# nRF52832_qfaa.net
KiCad netlist of a schematic drawn in EAGLE
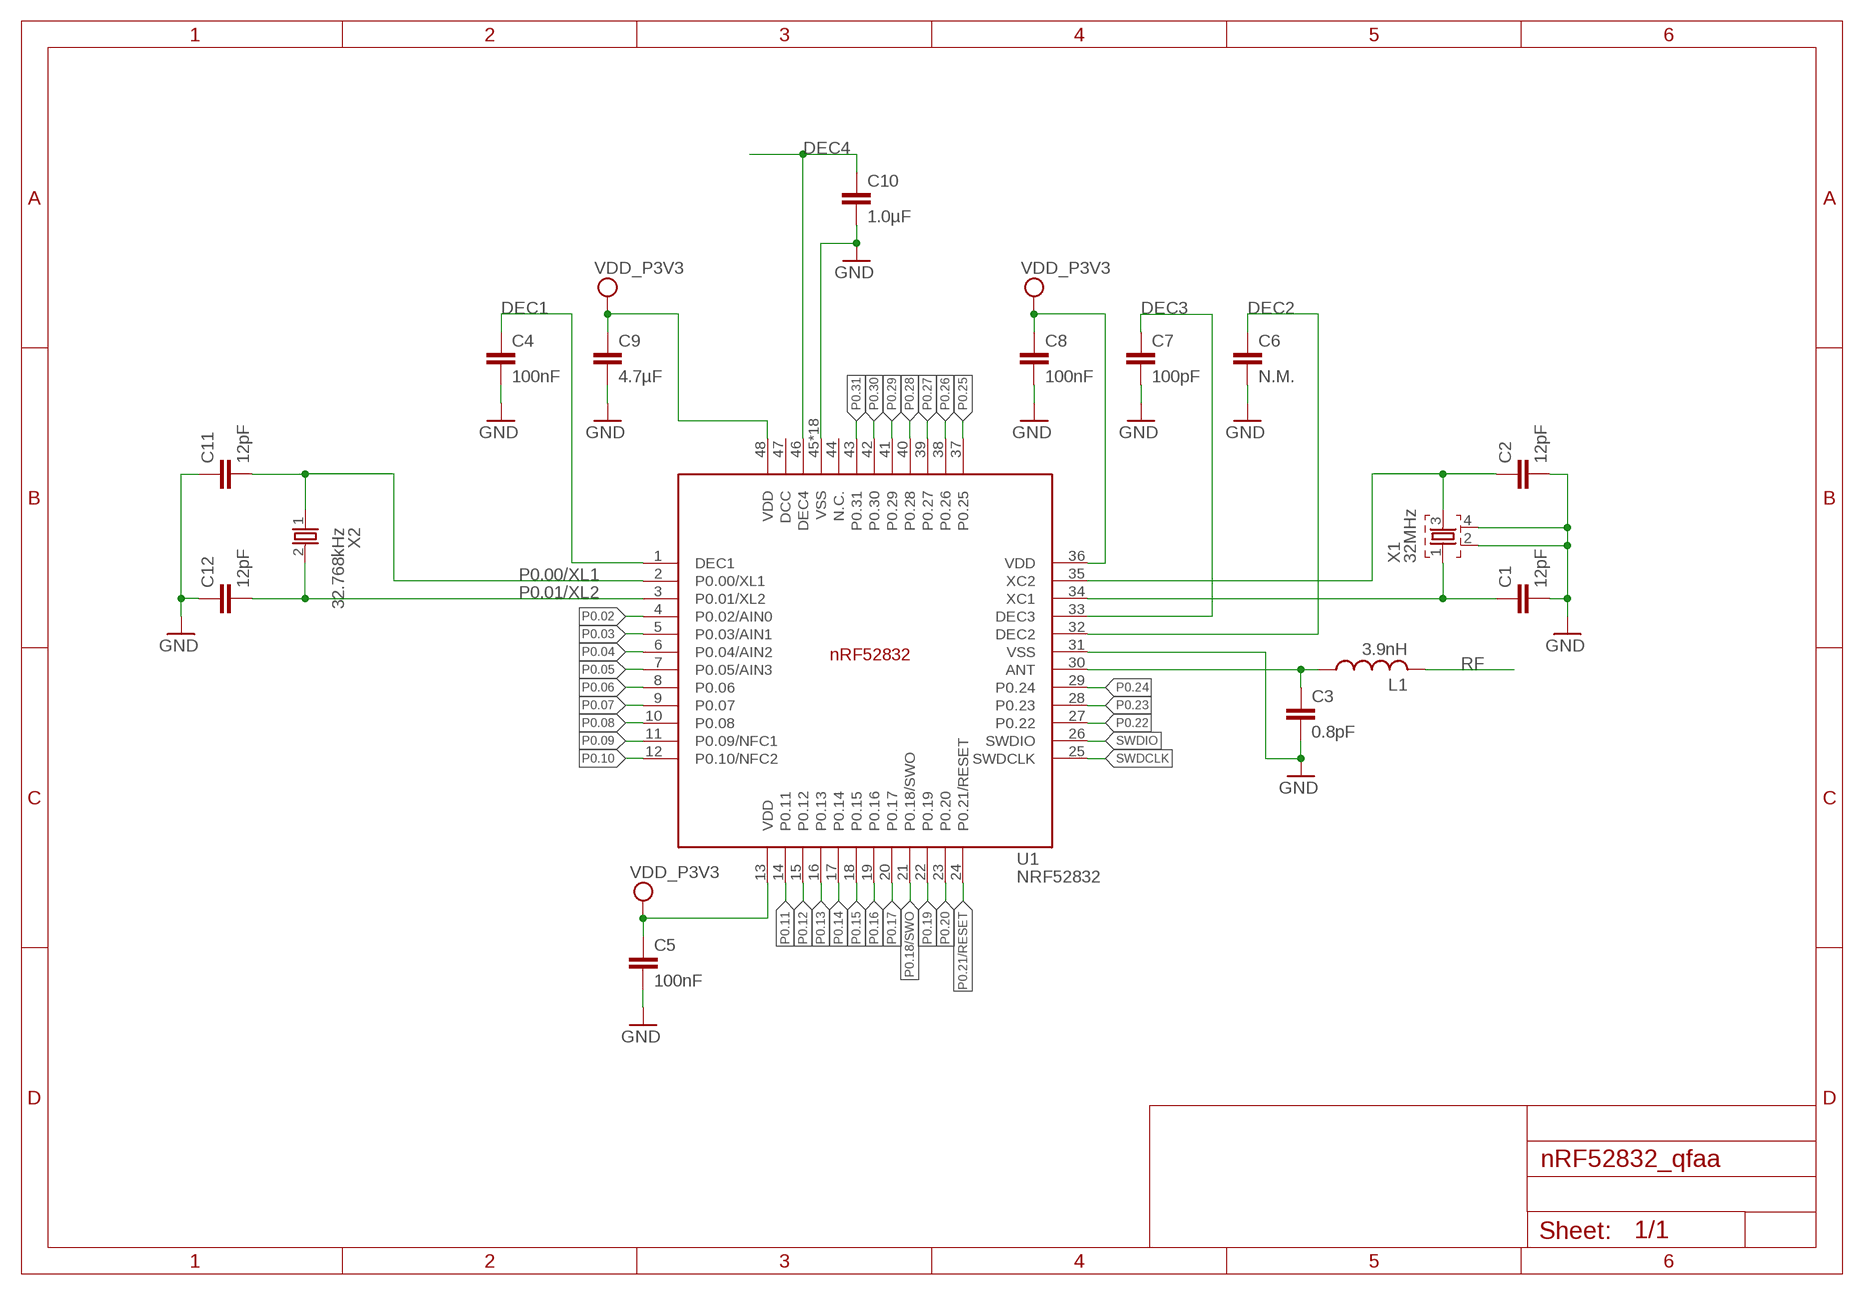
[diagram p0: schematic, sheet 1]

(export (version "E")
  (design (tool "Eeschema 10.0.6"))
  (components
    (comp (ref "C1")
      (value "12pF")
      (footprint "eagle-import:RESC0402_N")
      (libsource (lib "eagle-import") (part "CAPACITOR_0402_N"))
    )
    (comp (ref "C2")
      (value "12pF")
      (footprint "eagle-import:RESC0402_N")
      (libsource (lib "eagle-import") (part "CAPACITOR_0402_N"))
    )
    (comp (ref "C3")
      (value "0.8pF")
      (footprint "eagle-import:RESC0402_N")
      (libsource (lib "eagle-import") (part "CAPACITOR_0402_N"))
    )
    (comp (ref "C4")
      (value "100nF")
      (footprint "eagle-import:RESC0402_N")
      (libsource (lib "eagle-import") (part "CAPACITOR_0402_N"))
    )
    (comp (ref "C5")
      (value "100nF")
      (footprint "eagle-import:RESC0402_N")
      (libsource (lib "eagle-import") (part "CAPACITOR_0402_N"))
    )
    (comp (ref "C6")
      (value "N.M.")
      (footprint "eagle-import:RESC0402_N")
      (libsource (lib "eagle-import") (part "CAPACITOR_0402_N"))
    )
    (comp (ref "C7")
      (value "100pF")
      (footprint "eagle-import:RESC0402_N")
      (libsource (lib "eagle-import") (part "CAPACITOR_0402_N"))
    )
    (comp (ref "C8")
      (value "100nF")
      (footprint "eagle-import:RESC0402_N")
      (libsource (lib "eagle-import") (part "CAPACITOR_0402_N"))
    )
    (comp (ref "C9")
      (value "4.7µF")
      (footprint "eagle-import:RESC0603_N")
      (libsource (lib "eagle-import") (part "CAPACITOR_0603_N"))
    )
    (comp (ref "C10")
      (value "1.0µF")
      (footprint "eagle-import:RESC0603_N")
      (libsource (lib "eagle-import") (part "CAPACITOR_0603_N"))
    )
    (comp (ref "C11")
      (value "12pF")
      (footprint "eagle-import:RESC0402_N")
      (libsource (lib "eagle-import") (part "CAPACITOR_0402_N"))
    )
    (comp (ref "C12")
      (value "12pF")
      (footprint "eagle-import:RESC0402_N")
      (libsource (lib "eagle-import") (part "CAPACITOR_0402_N"))
    )
    (comp (ref "L1")
      (value "3.9nH")
      (footprint "eagle-import:RESC0402_N")
      (libsource (lib "eagle-import") (part "INDUCTOR_0402_N"))
    )
    (comp (ref "U1")
      (value "NRF52832")
      (footprint "eagle-import:QFN40P600X600X90-48_N")
      (libsource (lib "eagle-import") (part "NRF52832"))
    )
    (comp (ref "X1")
      (value "32MHz")
      (footprint "eagle-import:BT-XTAL_2016_N")
      (libsource (lib "eagle-import") (part "XTAL_32MHZ"))
    )
    (comp (ref "X2")
      (value "32.768kHz")
      (footprint "eagle-import:XTAL_3215_N")
      (libsource (lib "eagle-import") (part "XTAL_32KHZ"))
    )
  )
  (nets
    (net (code "1") (name "/DEC1") (class "Default")
      (node (ref "C4") (pin "1") (pinfunction "1_1") (pintype "passive"))
      (node (ref "U1") (pin "1") (pinfunction "DEC1_1") (pintype "power_in"))
    )
    (net (code "2") (name "/DEC2") (class "Default")
      (node (ref "C6") (pin "1") (pinfunction "1_1") (pintype "passive"))
      (node (ref "U1") (pin "32") (pinfunction "DEC2_32") (pintype "bidirectional"))
    )
    (net (code "3") (name "/DEC3") (class "Default")
      (node (ref "C7") (pin "1") (pinfunction "1_1") (pintype "passive"))
      (node (ref "U1") (pin "33") (pinfunction "DEC3_33") (pintype "bidirectional"))
    )
    (net (code "4") (name "/DEC4") (class "Default")
      (node (ref "C10") (pin "1") (pinfunction "1_1") (pintype "passive"))
      (node (ref "U1") (pin "46") (pinfunction "DEC4_46") (pintype "power_in"))
    )
    (net (code "5") (name "/P0.00{slash}XL1") (class "Default")
      (node (ref "C11") (pin "2") (pinfunction "2_2") (pintype "passive"))
      (node (ref "U1") (pin "2") (pinfunction "P0.00/XL1_2") (pintype "bidirectional"))
      (node (ref "X2") (pin "1") (pinfunction "1_1") (pintype "passive"))
    )
    (net (code "6") (name "/P0.01{slash}XL2") (class "Default")
      (node (ref "C12") (pin "2") (pinfunction "2_2") (pintype "passive"))
      (node (ref "U1") (pin "3") (pinfunction "P0.01/XL2_3") (pintype "bidirectional"))
      (node (ref "X2") (pin "2") (pinfunction "2_2") (pintype "passive"))
    )
    (net (code "7") (name "/RF") (class "Default")
      (node (ref "L1") (pin "2") (pinfunction "2_2") (pintype "passive"))
    )
    (net (code "8") (name "GND") (class "Default")
      (node (ref "C1") (pin "2") (pinfunction "2_2") (pintype "passive"))
      (node (ref "C10") (pin "2") (pinfunction "2_2") (pintype "passive"))
      (node (ref "C11") (pin "1") (pinfunction "1_1") (pintype "passive"))
      (node (ref "C12") (pin "1") (pinfunction "1_1") (pintype "passive"))
      (node (ref "C2") (pin "2") (pinfunction "2_2") (pintype "passive"))
      (node (ref "C3") (pin "2") (pinfunction "2_2") (pintype "passive"))
      (node (ref "C4") (pin "2") (pinfunction "2_2") (pintype "passive"))
      (node (ref "C5") (pin "2") (pinfunction "2_2") (pintype "passive"))
      (node (ref "C6") (pin "2") (pinfunction "2_2") (pintype "passive"))
      (node (ref "C7") (pin "2") (pinfunction "2_2") (pintype "passive"))
      (node (ref "C8") (pin "2") (pinfunction "2_2") (pintype "passive"))
      (node (ref "C9") (pin "2") (pinfunction "2_2") (pintype "passive"))
      (node (ref "U1") (pin "31") (pinfunction "VSS_31") (pintype "bidirectional"))
      (node (ref "U1") (pin "45") (pinfunction "VSS_45") (pintype "power_in"))
      (node (ref "U1") (pin "PAD") (pinfunction "VSS_PAD") (pintype "power_in"))
      (node (ref "U1") (pin "PAD@VIA01") (pinfunction "VSS_PAD@VIA01") (pintype "power_in"))
      (node (ref "U1") (pin "PAD@VIA02") (pinfunction "VSS_PAD@VIA02") (pintype "power_in"))
      (node (ref "U1") (pin "PAD@VIA03") (pinfunction "VSS_PAD@VIA03") (pintype "power_in"))
      (node (ref "U1") (pin "PAD@VIA04") (pinfunction "VSS_PAD@VIA04") (pintype "power_in"))
      (node (ref "U1") (pin "PAD@VIA05") (pinfunction "VSS_PAD@VIA05") (pintype "power_in"))
      (node (ref "U1") (pin "PAD@VIA06") (pinfunction "VSS_PAD@VIA06") (pintype "power_in"))
      (node (ref "U1") (pin "PAD@VIA07") (pinfunction "VSS_PAD@VIA07") (pintype "power_in"))
      (node (ref "U1") (pin "PAD@VIA08") (pinfunction "VSS_PAD@VIA08") (pintype "power_in"))
      (node (ref "U1") (pin "PAD@VIA09") (pinfunction "VSS_PAD@VIA09") (pintype "power_in"))
      (node (ref "U1") (pin "PAD@VIA10") (pinfunction "VSS_PAD@VIA10") (pintype "power_in"))
      (node (ref "U1") (pin "PAD@VIA11") (pinfunction "VSS_PAD@VIA11") (pintype "power_in"))
      (node (ref "U1") (pin "PAD@VIA12") (pinfunction "VSS_PAD@VIA12") (pintype "power_in"))
      (node (ref "U1") (pin "PAD@VIA13") (pinfunction "VSS_PAD@VIA13") (pintype "power_in"))
      (node (ref "U1") (pin "PAD@VIA14") (pinfunction "VSS_PAD@VIA14") (pintype "power_in"))
      (node (ref "U1") (pin "PAD@VIA15") (pinfunction "VSS_PAD@VIA15") (pintype "power_in"))
      (node (ref "U1") (pin "PAD@VIA16") (pinfunction "VSS_PAD@VIA16") (pintype "power_in"))
      (node (ref "X1") (pin "2") (pinfunction "2_2") (pintype "passive"))
      (node (ref "X1") (pin "4") (pinfunction "4_4") (pintype "passive"))
    )
    (net (code "9") (name "Net-(U1-ANT)") (class "Default")
      (node (ref "C3") (pin "1") (pinfunction "1_1") (pintype "passive"))
      (node (ref "L1") (pin "1") (pinfunction "1_1") (pintype "passive"))
      (node (ref "U1") (pin "30") (pinfunction "ANT_30") (pintype "bidirectional"))
    )
    (net (code "10") (name "Net-(U1-XC1)") (class "Default")
      (node (ref "C1") (pin "1") (pinfunction "1_1") (pintype "passive"))
      (node (ref "U1") (pin "34") (pinfunction "XC1_34") (pintype "input"))
      (node (ref "X1") (pin "1") (pinfunction "1_1") (pintype "passive"))
    )
    (net (code "11") (name "Net-(U1-XC2)") (class "Default")
      (node (ref "C2") (pin "1") (pinfunction "1_1") (pintype "passive"))
      (node (ref "U1") (pin "35") (pinfunction "XC2_35") (pintype "output"))
      (node (ref "X1") (pin "3") (pinfunction "3_3") (pintype "passive"))
    )
    (net (code "12") (name "P0.02") (class "Default")
      (node (ref "U1") (pin "4") (pinfunction "P0.02/AIN0_4") (pintype "bidirectional"))
    )
    (net (code "13") (name "P0.03") (class "Default")
      (node (ref "U1") (pin "5") (pinfunction "P0.03/AIN1_5") (pintype "bidirectional"))
    )
    (net (code "14") (name "P0.04") (class "Default")
      (node (ref "U1") (pin "6") (pinfunction "P0.04/AIN2_6") (pintype "bidirectional"))
    )
    (net (code "15") (name "P0.05") (class "Default")
      (node (ref "U1") (pin "7") (pinfunction "P0.05/AIN3_7") (pintype "bidirectional"))
    )
    (net (code "16") (name "P0.06") (class "Default")
      (node (ref "U1") (pin "8") (pinfunction "P0.06_8") (pintype "bidirectional"))
    )
    (net (code "17") (name "P0.07") (class "Default")
      (node (ref "U1") (pin "9") (pinfunction "P0.07_9") (pintype "bidirectional"))
    )
    (net (code "18") (name "P0.08") (class "Default")
      (node (ref "U1") (pin "10") (pinfunction "P0.08_10") (pintype "bidirectional"))
    )
    (net (code "19") (name "P0.09") (class "Default")
      (node (ref "U1") (pin "11") (pinfunction "P0.09/NFC1_11") (pintype "bidirectional"))
    )
    (net (code "20") (name "P0.10") (class "Default")
      (node (ref "U1") (pin "12") (pinfunction "P0.10/NFC2_12") (pintype "bidirectional"))
    )
    (net (code "21") (name "P0.11") (class "Default")
      (node (ref "U1") (pin "14") (pinfunction "P0.11_14") (pintype "bidirectional"))
    )
    (net (code "22") (name "P0.12") (class "Default")
      (node (ref "U1") (pin "15") (pinfunction "P0.12_15") (pintype "bidirectional"))
    )
    (net (code "23") (name "P0.13") (class "Default")
      (node (ref "U1") (pin "16") (pinfunction "P0.13_16") (pintype "bidirectional"))
    )
    (net (code "24") (name "P0.14") (class "Default")
      (node (ref "U1") (pin "17") (pinfunction "P0.14_17") (pintype "bidirectional"))
    )
    (net (code "25") (name "P0.15") (class "Default")
      (node (ref "U1") (pin "18") (pinfunction "P0.15_18") (pintype "bidirectional"))
    )
    (net (code "26") (name "P0.16") (class "Default")
      (node (ref "U1") (pin "19") (pinfunction "P0.16_19") (pintype "bidirectional"))
    )
    (net (code "27") (name "P0.17") (class "Default")
      (node (ref "U1") (pin "20") (pinfunction "P0.17_20") (pintype "bidirectional"))
    )
    (net (code "28") (name "P0.18{slash}SWO") (class "Default")
      (node (ref "U1") (pin "21") (pinfunction "P0.18/SWO_21") (pintype "bidirectional"))
    )
    (net (code "29") (name "P0.19") (class "Default")
      (node (ref "U1") (pin "22") (pinfunction "P0.19_22") (pintype "bidirectional"))
    )
    (net (code "30") (name "P0.20") (class "Default")
      (node (ref "U1") (pin "23") (pinfunction "P0.20_23") (pintype "bidirectional"))
    )
    (net (code "31") (name "P0.21{slash}RESET") (class "Default")
      (node (ref "U1") (pin "24") (pinfunction "P0.21/RESET_24") (pintype "bidirectional"))
    )
    (net (code "32") (name "P0.22") (class "Default")
      (node (ref "U1") (pin "27") (pinfunction "P0.22_27") (pintype "bidirectional"))
    )
    (net (code "33") (name "P0.23") (class "Default")
      (node (ref "U1") (pin "28") (pinfunction "P0.23_28") (pintype "bidirectional"))
    )
    (net (code "34") (name "P0.24") (class "Default")
      (node (ref "U1") (pin "29") (pinfunction "P0.24_29") (pintype "bidirectional"))
    )
    (net (code "35") (name "P0.25") (class "Default")
      (node (ref "U1") (pin "37") (pinfunction "P0.25_37") (pintype "bidirectional"))
    )
    (net (code "36") (name "P0.26") (class "Default")
      (node (ref "U1") (pin "38") (pinfunction "P0.26_38") (pintype "bidirectional"))
    )
    (net (code "37") (name "P0.27") (class "Default")
      (node (ref "U1") (pin "39") (pinfunction "P0.27_39") (pintype "bidirectional"))
    )
    (net (code "38") (name "P0.28") (class "Default")
      (node (ref "U1") (pin "40") (pinfunction "P0.28_40") (pintype "bidirectional"))
    )
    (net (code "39") (name "P0.29") (class "Default")
      (node (ref "U1") (pin "41") (pinfunction "P0.29_41") (pintype "bidirectional"))
    )
    (net (code "40") (name "P0.30") (class "Default")
      (node (ref "U1") (pin "42") (pinfunction "P0.30_42") (pintype "bidirectional"))
    )
    (net (code "41") (name "P0.31") (class "Default")
      (node (ref "U1") (pin "43") (pinfunction "P0.31_43") (pintype "bidirectional"))
    )
    (net (code "42") (name "SWDCLK") (class "Default")
      (node (ref "U1") (pin "25") (pinfunction "SWDCLK_25") (pintype "input"))
    )
    (net (code "43") (name "SWDIO") (class "Default")
      (node (ref "U1") (pin "26") (pinfunction "SWDIO_26") (pintype "bidirectional"))
    )
    (net (code "44") (name "VDD_P3V3") (class "Default")
      (node (ref "C5") (pin "1") (pinfunction "1_1") (pintype "passive"))
      (node (ref "C8") (pin "1") (pinfunction "1_1") (pintype "passive"))
      (node (ref "C9") (pin "1") (pinfunction "1_1") (pintype "passive"))
      (node (ref "U1") (pin "13") (pinfunction "VDD_13") (pintype "power_in"))
      (node (ref "U1") (pin "36") (pinfunction "VDD_36") (pintype "power_in"))
      (node (ref "U1") (pin "48") (pinfunction "VDD_48") (pintype "power_in"))
    )
    (net (code "45") (name "unconnected-(U1-DCC-Pad47)") (class "Default")
      (node (ref "U1") (pin "47") (pinfunction "DCC_47") (pintype "output"))
    )
    (net (code "46") (name "unconnected-(U1-N.C.-Pad44)") (class "Default")
      (node (ref "U1") (pin "44") (pinfunction "N.C._44") (pintype "no_connect"))
    )
  )
)
